# DiffController.net
KiCad netlist of a schematic drawn in EAGLE
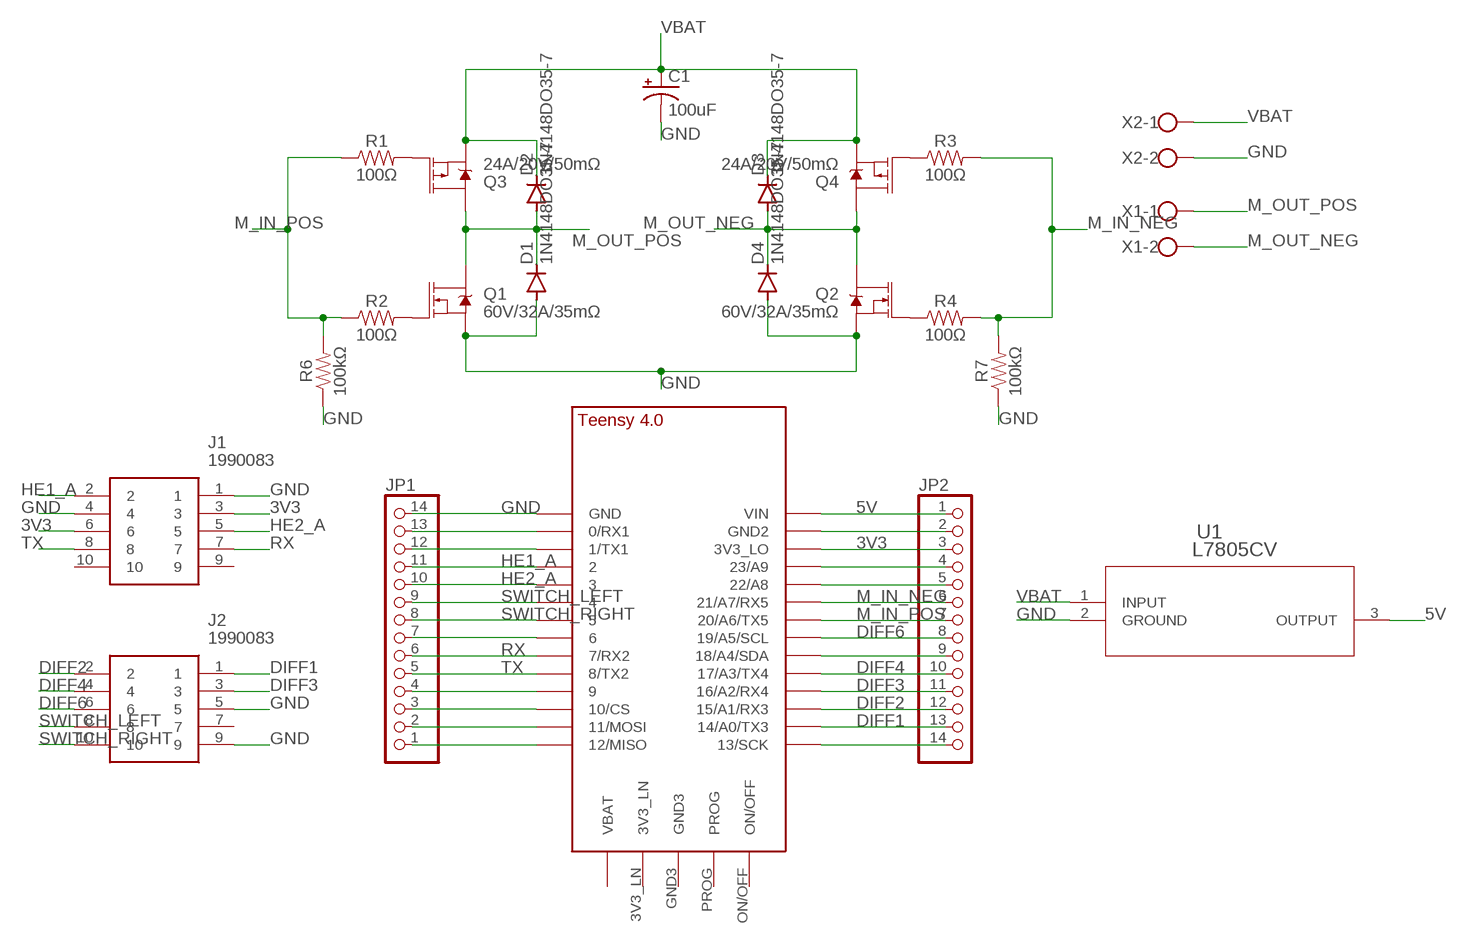
[diagram p0: schematic, sheet 1]

(export (version "E")
  (design (tool "Eeschema 10.0.6"))
  (components
    (comp (ref "C1")
      (value "100uF")
      (footprint "eagle-import:CPOL-RADIAL-2.5MM-6.5MM")
      (libsource (lib "eagle-import") (part "100UF-POLAR-RADIAL-2.5MM-25V-20%"))
    )
    (comp (ref "D1")
      (value "1N4148DO35-7")
      (footprint "eagle-import:DO35-7")
      (libsource (lib "eagle-import") (part "1N4148DO35-7"))
    )
    (comp (ref "D2")
      (value "1N4148DO35-7")
      (footprint "eagle-import:DO35-7")
      (libsource (lib "eagle-import") (part "1N4148DO35-7"))
    )
    (comp (ref "D3")
      (value "1N4148DO35-7")
      (footprint "eagle-import:DO35-7")
      (libsource (lib "eagle-import") (part "1N4148DO35-7"))
    )
    (comp (ref "D4")
      (value "1N4148DO35-7")
      (footprint "eagle-import:DO35-7")
      (libsource (lib "eagle-import") (part "1N4148DO35-7"))
    )
    (comp (ref "J1")
      (value "1990083")
      (footprint "eagle-import:1990083")
      (fields (field (name "MOUSER_PART_NUMBER") "651-1990083"))
      (libsource (lib "eagle-import") (part "1990083"))
    )
    (comp (ref "J2")
      (value "1990083")
      (footprint "eagle-import:1990083")
      (fields (field (name "MOUSER_PART_NUMBER") "651-1990083"))
      (libsource (lib "eagle-import") (part "1990083"))
    )
    (comp (ref "JP1")
      (value "PINHD-1X14")
      (footprint "eagle-import:1X14")
      (libsource (lib "eagle-import") (part "PINHD-1X14"))
    )
    (comp (ref "JP2")
      (value "PINHD-1X14")
      (footprint "eagle-import:1X14")
      (libsource (lib "eagle-import") (part "PINHD-1X14"))
    )
    (comp (ref "Q1")
      (value "60V/32A/35mΩ")
      (footprint "eagle-import:TO220V")
      (libsource (lib "eagle-import") (part "MOSFET-NCH-FQP30N06L"))
    )
    (comp (ref "Q2")
      (value "60V/32A/35mΩ")
      (footprint "eagle-import:TO220V")
      (libsource (lib "eagle-import") (part "MOSFET-NCH-FQP30N06L"))
    )
    (comp (ref "Q3")
      (value "24A/20V/50mΩ")
      (footprint "eagle-import:TO220V")
      (libsource (lib "eagle-import") (part "MOSFET_PCH-NDP6020P"))
    )
    (comp (ref "Q4")
      (value "24A/20V/50mΩ")
      (footprint "eagle-import:TO220V")
      (libsource (lib "eagle-import") (part "MOSFET_PCH-NDP6020P"))
    )
    (comp (ref "R1")
      (value "100Ω")
      (footprint "eagle-import:AXIAL-0.3")
      (libsource (lib "eagle-import") (part "RESISTORAXIAL-0.3"))
    )
    (comp (ref "R2")
      (value "100Ω")
      (footprint "eagle-import:AXIAL-0.3")
      (libsource (lib "eagle-import") (part "RESISTORAXIAL-0.3"))
    )
    (comp (ref "R3")
      (value "100Ω")
      (footprint "eagle-import:AXIAL-0.3")
      (libsource (lib "eagle-import") (part "RESISTORAXIAL-0.3"))
    )
    (comp (ref "R4")
      (value "100Ω")
      (footprint "eagle-import:AXIAL-0.3")
      (libsource (lib "eagle-import") (part "RESISTORAXIAL-0.3"))
    )
    (comp (ref "R6")
      (value "100kΩ")
      (footprint "eagle-import:AXIAL-0.3")
      (libsource (lib "eagle-import") (part "RESISTORAXIAL-0.3"))
    )
    (comp (ref "R7")
      (value "100kΩ")
      (footprint "eagle-import:AXIAL-0.3")
      (libsource (lib "eagle-import") (part "RESISTORAXIAL-0.3"))
    )
    (comp (ref "U$2")
      (value "TEENSY_4.0_EXPANDED_1")
      (footprint "eagle-import:TEENSY_4.0_EXPANDED_1")
      (libsource (lib "eagle-import") (part "TEENSY_4.0_EXPANDED_1"))
    )
    (comp (ref "U1")
      (value "L7805CV")
      (footprint "eagle-import:TO-220_STM")
      (libsource (lib "eagle-import") (part "L7805CV"))
    )
    (comp (ref "X1")
      (value "W237-102")
      (footprint "eagle-import:W237-102")
      (fields (field (name "MPN") "237-102"))
      (libsource (lib "eagle-import") (part "W237-102"))
    )
    (comp (ref "X2")
      (value "W237-102")
      (footprint "eagle-import:W237-102")
      (fields (field (name "MPN") "237-102"))
      (libsource (lib "eagle-import") (part "W237-102"))
    )
  )
  (nets
    (net (code "1") (name "/3V3") (class "Default")
      (node (ref "J1") (pin "3") (pinfunction "3_3") (pintype "bidirectional"))
      (node (ref "J1") (pin "6") (pinfunction "6_6") (pintype "bidirectional"))
      (node (ref "JP2") (pin "3") (pinfunction "3_3") (pintype "passive"))
      (node (ref "U$2") (pin "3V3_LO") (pinfunction "3V3_LO_3V3_LO") (pintype "bidirectional"))
    )
    (net (code "2") (name "/5V") (class "Default")
      (node (ref "JP2") (pin "1") (pinfunction "1_1") (pintype "passive"))
      (node (ref "U$2") (pin "VIN") (pinfunction "VIN_VIN") (pintype "bidirectional"))
      (node (ref "U1") (pin "3") (pinfunction "OUTPUT_3") (pintype "output"))
    )
    (net (code "3") (name "/DIFF1") (class "Default")
      (node (ref "J2") (pin "1") (pinfunction "1_1") (pintype "bidirectional"))
      (node (ref "JP2") (pin "13") (pinfunction "13_13") (pintype "passive"))
      (node (ref "U$2") (pin "14/A0") (pinfunction "14/A0/TX3_14/A0") (pintype "bidirectional"))
    )
    (net (code "4") (name "/DIFF2") (class "Default")
      (node (ref "J2") (pin "2") (pinfunction "2_2") (pintype "bidirectional"))
      (node (ref "JP2") (pin "12") (pinfunction "12_12") (pintype "passive"))
      (node (ref "U$2") (pin "15/A1") (pinfunction "15/A1/RX3_15/A1") (pintype "bidirectional"))
    )
    (net (code "5") (name "/DIFF3") (class "Default")
      (node (ref "J2") (pin "3") (pinfunction "3_3") (pintype "bidirectional"))
      (node (ref "JP2") (pin "11") (pinfunction "11_11") (pintype "passive"))
      (node (ref "U$2") (pin "16/A2") (pinfunction "16/A2/RX4_16/A2") (pintype "bidirectional"))
    )
    (net (code "6") (name "/DIFF4") (class "Default")
      (node (ref "J2") (pin "4") (pinfunction "4_4") (pintype "bidirectional"))
      (node (ref "JP2") (pin "10") (pinfunction "10_10") (pintype "passive"))
      (node (ref "U$2") (pin "17/A3") (pinfunction "17/A3/TX4_17/A3") (pintype "bidirectional"))
    )
    (net (code "7") (name "/DIFF6") (class "Default")
      (node (ref "J2") (pin "6") (pinfunction "6_6") (pintype "bidirectional"))
      (node (ref "JP2") (pin "8") (pinfunction "8_8") (pintype "passive"))
      (node (ref "U$2") (pin "19/A5/SCL") (pinfunction "19/A5/SCL_19/A5/SCL") (pintype "bidirectional"))
    )
    (net (code "8") (name "/GND") (class "Default")
      (node (ref "C1") (pin "2") (pinfunction "-_2") (pintype "passive"))
      (node (ref "D1") (pin "A") (pinfunction "A_A") (pintype "passive"))
      (node (ref "D4") (pin "A") (pinfunction "A_A") (pintype "passive"))
      (node (ref "J1") (pin "1") (pinfunction "1_1") (pintype "bidirectional"))
      (node (ref "J1") (pin "4") (pinfunction "4_4") (pintype "bidirectional"))
      (node (ref "J2") (pin "5") (pinfunction "5_5") (pintype "bidirectional"))
      (node (ref "J2") (pin "9") (pinfunction "9_9") (pintype "bidirectional"))
      (node (ref "JP1") (pin "14") (pinfunction "14_14") (pintype "passive"))
      (node (ref "Q1") (pin "3") (pinfunction "S_3") (pintype "bidirectional"))
      (node (ref "Q2") (pin "3") (pinfunction "S_3") (pintype "bidirectional"))
      (node (ref "R6") (pin "P$1") (pinfunction "1_P$1") (pintype "passive"))
      (node (ref "R7") (pin "P$1") (pinfunction "1_P$1") (pintype "passive"))
      (node (ref "U$2") (pin "GND") (pinfunction "GND_GND") (pintype "bidirectional"))
      (node (ref "U1") (pin "2") (pinfunction "GROUND_2") (pintype "passive"))
      (node (ref "X2") (pin "2") (pinfunction "KL_2") (pintype "passive"))
    )
    (net (code "9") (name "/HE1_A") (class "Default")
      (node (ref "J1") (pin "2") (pinfunction "2_2") (pintype "bidirectional"))
      (node (ref "JP1") (pin "11") (pinfunction "11_11") (pintype "passive"))
      (node (ref "U$2") (pin "2") (pinfunction "2_2") (pintype "bidirectional"))
    )
    (net (code "10") (name "/HE2_A") (class "Default")
      (node (ref "J1") (pin "5") (pinfunction "5_5") (pintype "bidirectional"))
      (node (ref "JP1") (pin "10") (pinfunction "10_10") (pintype "passive"))
      (node (ref "U$2") (pin "3/CANTX") (pinfunction "3_3/CANTX") (pintype "bidirectional"))
    )
    (net (code "11") (name "/M_IN_NEG") (class "Default")
      (node (ref "JP2") (pin "6") (pinfunction "6_6") (pintype "passive"))
      (node (ref "R3") (pin "P$2") (pinfunction "2_P$2") (pintype "passive"))
      (node (ref "R4") (pin "P$2") (pinfunction "2_P$2") (pintype "passive"))
      (node (ref "R7") (pin "P$2") (pinfunction "2_P$2") (pintype "passive"))
      (node (ref "U$2") (pin "21/A7") (pinfunction "21/A7/RX5_21/A7") (pintype "bidirectional"))
    )
    (net (code "12") (name "/M_IN_POS") (class "Default")
      (node (ref "JP2") (pin "7") (pinfunction "7_7") (pintype "passive"))
      (node (ref "R1") (pin "P$1") (pinfunction "1_P$1") (pintype "passive"))
      (node (ref "R2") (pin "P$1") (pinfunction "1_P$1") (pintype "passive"))
      (node (ref "R6") (pin "P$2") (pinfunction "2_P$2") (pintype "passive"))
      (node (ref "U$2") (pin "20/A6") (pinfunction "20/A6/TX5_20/A6") (pintype "bidirectional"))
    )
    (net (code "13") (name "/M_OUT_NEG") (class "Default")
      (node (ref "D3") (pin "A") (pinfunction "A_A") (pintype "passive"))
      (node (ref "D4") (pin "C") (pinfunction "C_C") (pintype "passive"))
      (node (ref "Q2") (pin "2") (pinfunction "D_2") (pintype "bidirectional"))
      (node (ref "Q4") (pin "2") (pinfunction "D_2") (pintype "bidirectional"))
      (node (ref "X1") (pin "2") (pinfunction "KL_2") (pintype "passive"))
    )
    (net (code "14") (name "/M_OUT_POS") (class "Default")
      (node (ref "D1") (pin "C") (pinfunction "C_C") (pintype "passive"))
      (node (ref "D2") (pin "A") (pinfunction "A_A") (pintype "passive"))
      (node (ref "Q1") (pin "2") (pinfunction "D_2") (pintype "bidirectional"))
      (node (ref "Q3") (pin "2") (pinfunction "D_2") (pintype "bidirectional"))
      (node (ref "X1") (pin "1") (pinfunction "KL_1") (pintype "passive"))
    )
    (net (code "15") (name "/RX") (class "Default")
      (node (ref "J1") (pin "7") (pinfunction "7_7") (pintype "bidirectional"))
      (node (ref "JP1") (pin "6") (pinfunction "6_6") (pintype "passive"))
      (node (ref "U$2") (pin "7") (pinfunction "7/RX2_7") (pintype "bidirectional"))
    )
    (net (code "16") (name "/SWITCH_LEFT") (class "Default")
      (node (ref "J2") (pin "8") (pinfunction "8_8") (pintype "bidirectional"))
      (node (ref "JP1") (pin "9") (pinfunction "9_9") (pintype "passive"))
      (node (ref "U$2") (pin "4/CANRX") (pinfunction "4_4/CANRX") (pintype "bidirectional"))
    )
    (net (code "17") (name "/SWITCH_RIGHT") (class "Default")
      (node (ref "J2") (pin "10") (pinfunction "10_10") (pintype "bidirectional"))
      (node (ref "JP1") (pin "8") (pinfunction "8_8") (pintype "passive"))
      (node (ref "U$2") (pin "5") (pinfunction "5_5") (pintype "bidirectional"))
    )
    (net (code "18") (name "/TX") (class "Default")
      (node (ref "J1") (pin "8") (pinfunction "8_8") (pintype "bidirectional"))
      (node (ref "JP1") (pin "5") (pinfunction "5_5") (pintype "passive"))
      (node (ref "U$2") (pin "8") (pinfunction "8/TX2_8") (pintype "bidirectional"))
    )
    (net (code "19") (name "/VBAT") (class "Default")
      (node (ref "C1") (pin "1") (pinfunction "+_1") (pintype "passive"))
      (node (ref "D2") (pin "C") (pinfunction "C_C") (pintype "passive"))
      (node (ref "D3") (pin "C") (pinfunction "C_C") (pintype "passive"))
      (node (ref "Q3") (pin "3") (pinfunction "S_3") (pintype "bidirectional"))
      (node (ref "Q4") (pin "3") (pinfunction "S_3") (pintype "bidirectional"))
      (node (ref "U1") (pin "1") (pinfunction "INPUT_1") (pintype "input"))
      (node (ref "X2") (pin "1") (pinfunction "KL_1") (pintype "passive"))
    )
    (net (code "20") (name "Net-(JP1-Pad1)") (class "Default")
      (node (ref "JP1") (pin "1") (pinfunction "1_1") (pintype "passive"))
      (node (ref "U$2") (pin "12/MISO") (pinfunction "12/MISO_12/MISO") (pintype "bidirectional"))
    )
    (net (code "21") (name "Net-(JP1-Pad2)") (class "Default")
      (node (ref "JP1") (pin "2") (pinfunction "2_2") (pintype "passive"))
      (node (ref "U$2") (pin "11/MOSI") (pinfunction "11/MOSI_11/MOSI") (pintype "bidirectional"))
    )
    (net (code "22") (name "Net-(JP1-Pad3)") (class "Default")
      (node (ref "JP1") (pin "3") (pinfunction "3_3") (pintype "passive"))
      (node (ref "U$2") (pin "10/CS") (pinfunction "10/CS_10/CS") (pintype "bidirectional"))
    )
    (net (code "23") (name "Net-(JP1-Pad7)") (class "Default")
      (node (ref "JP1") (pin "7") (pinfunction "7_7") (pintype "passive"))
      (node (ref "U$2") (pin "6") (pinfunction "6_6") (pintype "bidirectional"))
    )
    (net (code "24") (name "Net-(JP2-Pad2)") (class "Default")
      (node (ref "JP2") (pin "2") (pinfunction "2_2") (pintype "passive"))
      (node (ref "U$2") (pin "GND2") (pinfunction "GND2_GND2") (pintype "bidirectional"))
    )
    (net (code "25") (name "Net-(JP2-Pad4)") (class "Default")
      (node (ref "JP2") (pin "4") (pinfunction "4_4") (pintype "passive"))
      (node (ref "U$2") (pin "23/A9") (pinfunction "23/A9_23/A9") (pintype "bidirectional"))
    )
    (net (code "26") (name "Net-(JP2-Pad5)") (class "Default")
      (node (ref "JP2") (pin "5") (pinfunction "5_5") (pintype "passive"))
      (node (ref "U$2") (pin "22/A8") (pinfunction "22/A8_22/A8") (pintype "bidirectional"))
    )
    (net (code "27") (name "Net-(JP2-Pad9)") (class "Default")
      (node (ref "JP2") (pin "9") (pinfunction "9_9") (pintype "passive"))
      (node (ref "U$2") (pin "18/A4/SDA") (pinfunction "18/A4/SDA_18/A4/SDA") (pintype "bidirectional"))
    )
    (net (code "28") (name "Net-(JP2-Pad14)") (class "Default")
      (node (ref "JP2") (pin "14") (pinfunction "14_14") (pintype "passive"))
      (node (ref "U$2") (pin "13/SCK") (pinfunction "13/SCK_13/SCK") (pintype "bidirectional"))
    )
    (net (code "29") (name "Net-(Q1-G)") (class "Default")
      (node (ref "Q1") (pin "1") (pinfunction "G_1") (pintype "bidirectional"))
      (node (ref "R2") (pin "P$2") (pinfunction "2_P$2") (pintype "passive"))
    )
    (net (code "30") (name "Net-(Q2-G)") (class "Default")
      (node (ref "Q2") (pin "1") (pinfunction "G_1") (pintype "bidirectional"))
      (node (ref "R4") (pin "P$1") (pinfunction "1_P$1") (pintype "passive"))
    )
    (net (code "31") (name "Net-(Q3-G)") (class "Default")
      (node (ref "Q3") (pin "1") (pinfunction "G_1") (pintype "bidirectional"))
      (node (ref "R1") (pin "P$2") (pinfunction "2_P$2") (pintype "passive"))
    )
    (net (code "32") (name "Net-(Q4-G)") (class "Default")
      (node (ref "Q4") (pin "1") (pinfunction "G_1") (pintype "bidirectional"))
      (node (ref "R3") (pin "P$1") (pinfunction "1_P$1") (pintype "passive"))
    )
    (net (code "33") (name "Net-(U$2-0{slash}RX1)") (class "Default")
      (node (ref "JP1") (pin "13") (pinfunction "13_13") (pintype "passive"))
      (node (ref "U$2") (pin "0/RX") (pinfunction "0/RX1_0/RX") (pintype "bidirectional"))
    )
    (net (code "34") (name "Net-(U$2-1{slash}TX1)") (class "Default")
      (node (ref "JP1") (pin "12") (pinfunction "12_12") (pintype "passive"))
      (node (ref "U$2") (pin "1/TX") (pinfunction "1/TX1_1/TX") (pintype "bidirectional"))
    )
    (net (code "35") (name "Net-(U$2-9)") (class "Default")
      (node (ref "JP1") (pin "4") (pinfunction "4_4") (pintype "passive"))
      (node (ref "U$2") (pin "9/CS") (pinfunction "9_9/CS") (pintype "bidirectional"))
    )
    (net (code "36") (name "unconnected-(J1-Pad9)") (class "Default")
      (node (ref "J1") (pin "9") (pinfunction "9_9") (pintype "bidirectional"))
    )
    (net (code "37") (name "unconnected-(J1-Pad10)") (class "Default")
      (node (ref "J1") (pin "10") (pinfunction "10_10") (pintype "bidirectional"))
    )
    (net (code "38") (name "unconnected-(J2-Pad7)") (class "Default")
      (node (ref "J2") (pin "7") (pinfunction "7_7") (pintype "bidirectional"))
    )
    (net (code "39") (name "unconnected-(U$2-Pad3V3_LN)") (class "Default")
      (node (ref "U$2") (pin "3V3_LN") (pinfunction "3V3_LN_3V3_LN") (pintype "bidirectional"))
    )
    (net (code "40") (name "unconnected-(U$2-PadGND3)") (class "Default")
      (node (ref "U$2") (pin "GND3") (pinfunction "GND3_GND3") (pintype "bidirectional"))
    )
    (net (code "41") (name "unconnected-(U$2-PadON{slash}OFF)") (class "Default")
      (node (ref "U$2") (pin "ON/OFF") (pinfunction "ON/OFF_ON/OFF") (pintype "bidirectional"))
    )
    (net (code "42") (name "unconnected-(U$2-PadPROG)") (class "Default")
      (node (ref "U$2") (pin "PROG") (pinfunction "PROG_PROG") (pintype "bidirectional"))
    )
    (net (code "43") (name "unconnected-(U$2-VBAT-PadVBAT\\)") (class "Default")
      (node (ref "U$2") (pin "VBAT\\") (pinfunction "VBAT_VBAT\\") (pintype "bidirectional"))
    )
  )
)
